# cj125.net
KiCad netlist of a schematic drawn in Altium Designer
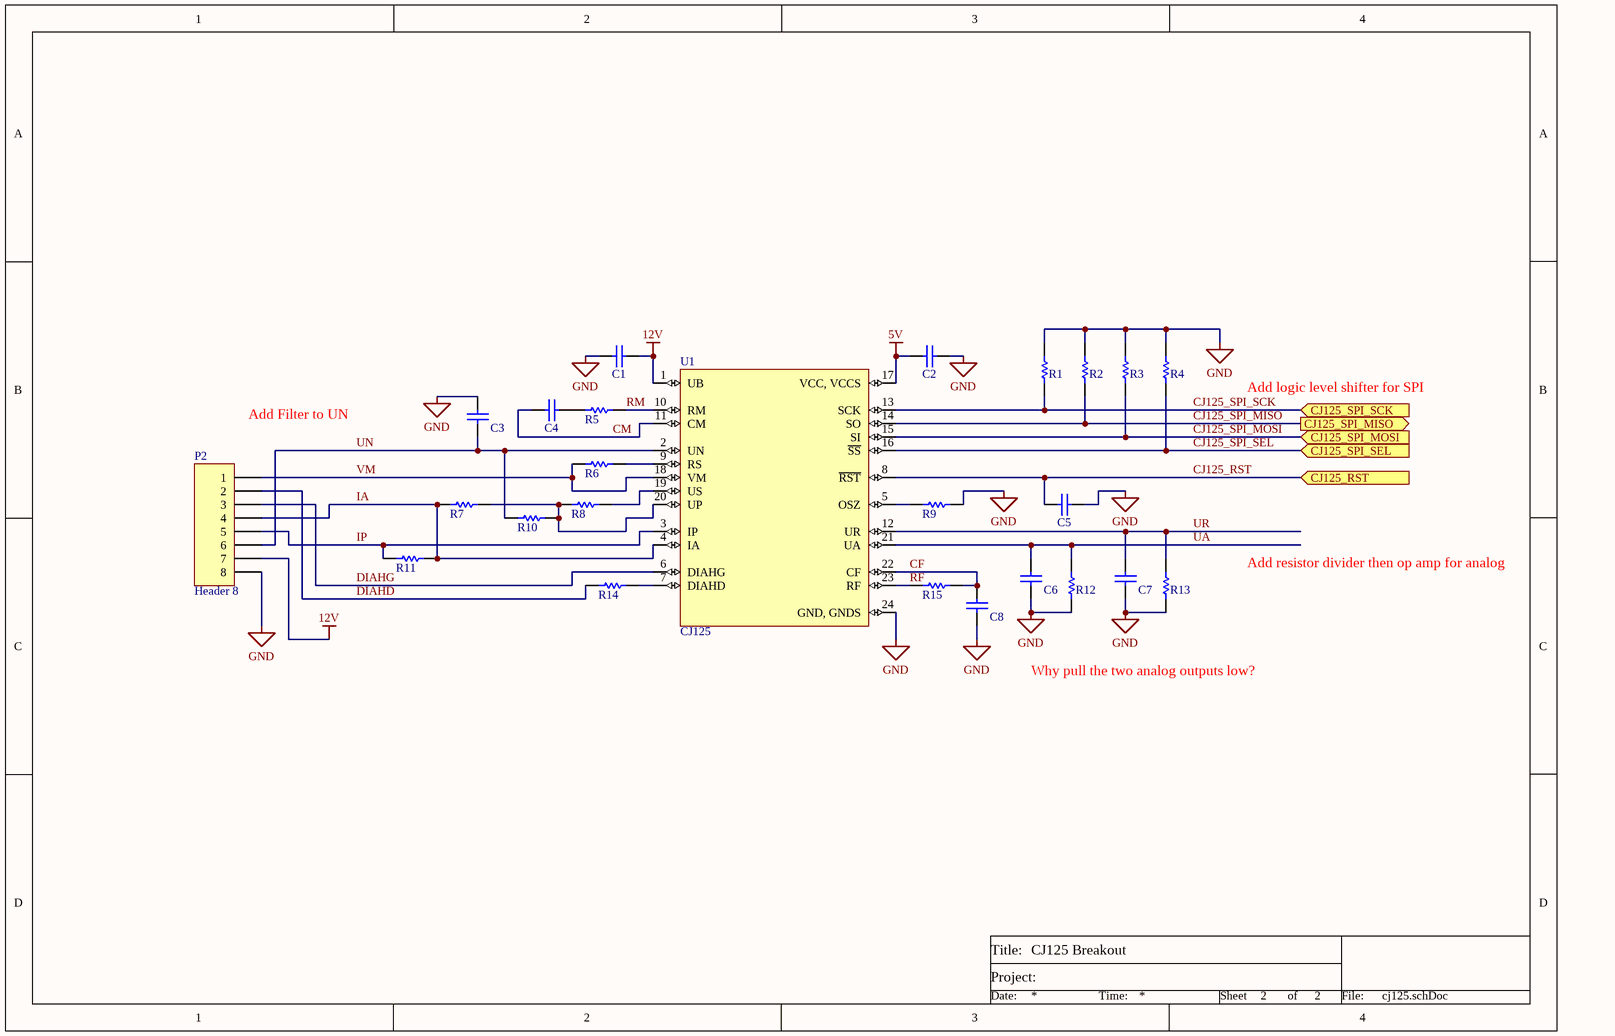
[diagram p0: cj125.schDoc]

(export (version "E")
  (design (tool "Eeschema 10.0.6"))
  (components
    (comp (ref "C1")
      (value "Generic 0805 Capacitor")
      (footprint "0805")
      (libsource (lib "symbol_library") (part "C_0805"))
    )
    (comp (ref "C2")
      (value "Generic 0805 Capacitor")
      (footprint "0805")
      (libsource (lib "symbol_library") (part "C_0805"))
    )
    (comp (ref "C3")
      (value "Generic 0805 Capacitor")
      (footprint "0805")
      (libsource (lib "symbol_library") (part "C_0805"))
    )
    (comp (ref "C4")
      (value "Generic 0805 Capacitor")
      (footprint "0805")
      (libsource (lib "symbol_library") (part "C_0805"))
    )
    (comp (ref "C5")
      (value "Generic 0805 Capacitor")
      (footprint "0805")
      (libsource (lib "symbol_library") (part "C_0805"))
    )
    (comp (ref "C6")
      (value "Generic 0805 Capacitor")
      (footprint "0805")
      (libsource (lib "symbol_library") (part "C_0805"))
    )
    (comp (ref "C7")
      (value "Generic 0805 Capacitor")
      (footprint "0805")
      (libsource (lib "symbol_library") (part "C_0805"))
    )
    (comp (ref "C8")
      (value "Generic 0805 Capacitor")
      (footprint "0805")
      (libsource (lib "symbol_library") (part "C_0805"))
    )
    (comp (ref "P2")
      (value "Header 8")
      (footprint "HDR1X8")
      (description "Header, 8-Pin")
      (fields (field (name "PUBLISHER") "Altium Limited"))
      (libsource (lib "Miscellaneous Connectors") (part "Header 8"))
    )
    (comp (ref "R1")
      (value "Generic 0603 Resistor")
      (footprint "0603")
      (libsource (lib "symbol_library") (part "R_0603"))
    )
    (comp (ref "R2")
      (value "Generic 0603 Resistor")
      (footprint "0603")
      (libsource (lib "symbol_library") (part "R_0603"))
    )
    (comp (ref "R3")
      (value "Generic 0603 Resistor")
      (footprint "0603")
      (libsource (lib "symbol_library") (part "R_0603"))
    )
    (comp (ref "R4")
      (value "Generic 0603 Resistor")
      (footprint "0603")
      (libsource (lib "symbol_library") (part "R_0603"))
    )
    (comp (ref "R5")
      (value "Generic 0603 Resistor")
      (footprint "0603")
      (libsource (lib "symbol_library") (part "R_0603"))
    )
    (comp (ref "R6")
      (value "Generic 0603 Resistor")
      (footprint "0603")
      (libsource (lib "symbol_library") (part "R_0603"))
    )
    (comp (ref "R7")
      (value "Generic 0603 Resistor")
      (footprint "0603")
      (libsource (lib "symbol_library") (part "R_0603"))
    )
    (comp (ref "R8")
      (value "Generic 0603 Resistor")
      (footprint "0603")
      (libsource (lib "symbol_library") (part "R_0603"))
    )
    (comp (ref "R9")
      (value "Generic 0603 Resistor")
      (footprint "0603")
      (libsource (lib "symbol_library") (part "R_0603"))
    )
    (comp (ref "R10")
      (value "Generic 0603 Resistor")
      (footprint "0603")
      (libsource (lib "symbol_library") (part "R_0603"))
    )
    (comp (ref "R11")
      (value "Generic 0603 Resistor")
      (footprint "0603")
      (libsource (lib "symbol_library") (part "R_0603"))
    )
    (comp (ref "R12")
      (value "Generic 0603 Resistor")
      (footprint "0603")
      (libsource (lib "symbol_library") (part "R_0603"))
    )
    (comp (ref "R13")
      (value "Generic 0603 Resistor")
      (footprint "0603")
      (libsource (lib "symbol_library") (part "R_0603"))
    )
    (comp (ref "R14")
      (value "Generic 0603 Resistor")
      (footprint "0603")
      (libsource (lib "symbol_library") (part "R_0603"))
    )
    (comp (ref "R15")
      (value "Generic 0603 Resistor")
      (footprint "0603")
      (libsource (lib "symbol_library") (part "R_0603"))
    )
    (comp (ref "U1")
      (value "CJ125")
      (footprint "SOIC-24")
      (description "5V 2Mbaud SMT Lambda Probe Interface IC - SOIC-24")
      (libsource (lib "symbol_library") (part "CJ125"))
    )
  )
  (nets
    (net (code "1") (name "/CF") (class "Default")
      (node (ref "C8") (pin "2") (pinfunction "2_2") (pintype "passive"))
      (node (ref "R15") (pin "2") (pinfunction "2_2") (pintype "passive"))
      (node (ref "U1") (pin "22") (pinfunction "CF_22") (pintype "bidirectional"))
    )
    (net (code "2") (name "/CJ125_RST") (class "Default")
      (node (ref "C5") (pin "1") (pinfunction "1_1") (pintype "passive"))
      (node (ref "U1") (pin "8") (pinfunction "~{RST}_8") (pintype "bidirectional"))
    )
    (net (code "3") (name "/CJ125_SPI_MISO") (class "Default")
      (node (ref "R2") (pin "1") (pinfunction "1_1") (pintype "passive"))
      (node (ref "U1") (pin "14") (pinfunction "SO_14") (pintype "bidirectional"))
    )
    (net (code "4") (name "/CJ125_SPI_MOSI") (class "Default")
      (node (ref "R3") (pin "1") (pinfunction "1_1") (pintype "passive"))
      (node (ref "U1") (pin "15") (pinfunction "SI_15") (pintype "bidirectional"))
    )
    (net (code "5") (name "/CJ125_SPI_SCK") (class "Default")
      (node (ref "R1") (pin "1") (pinfunction "1_1") (pintype "passive"))
      (node (ref "U1") (pin "13") (pinfunction "SCK_13") (pintype "bidirectional"))
    )
    (net (code "6") (name "/CJ125_SPI_SEL") (class "Default")
      (node (ref "R4") (pin "1") (pinfunction "1_1") (pintype "passive"))
      (node (ref "U1") (pin "16") (pinfunction "~{SS}_16") (pintype "bidirectional"))
    )
    (net (code "7") (name "/CM") (class "Default")
      (node (ref "C4") (pin "1") (pinfunction "1_1") (pintype "passive"))
      (node (ref "U1") (pin "11") (pinfunction "CM_11") (pintype "bidirectional"))
    )
    (net (code "8") (name "/DIAHD") (class "Default")
      (node (ref "P2") (pin "2") (pinfunction "2_2") (pintype "passive"))
      (node (ref "R14") (pin "1") (pinfunction "1_1") (pintype "passive"))
    )
    (net (code "9") (name "/DIAHG") (class "Default")
      (node (ref "P2") (pin "3") (pinfunction "3_3") (pintype "passive"))
      (node (ref "U1") (pin "6") (pinfunction "DIAHG_6") (pintype "bidirectional"))
    )
    (net (code "10") (name "/IA") (class "Default")
      (node (ref "P2") (pin "4") (pinfunction "4_4") (pintype "passive"))
      (node (ref "R11") (pin "2") (pinfunction "2_2") (pintype "passive"))
      (node (ref "R7") (pin "1") (pinfunction "1_1") (pintype "passive"))
      (node (ref "U1") (pin "4") (pinfunction "IA_4") (pintype "bidirectional"))
    )
    (net (code "11") (name "/IP") (class "Default")
      (node (ref "P2") (pin "5") (pinfunction "5_5") (pintype "passive"))
      (node (ref "R11") (pin "1") (pinfunction "1_1") (pintype "passive"))
      (node (ref "U1") (pin "3") (pinfunction "IP_3") (pintype "bidirectional"))
    )
    (net (code "12") (name "/RF") (class "Default")
      (node (ref "R15") (pin "1") (pinfunction "1_1") (pintype "passive"))
      (node (ref "U1") (pin "23") (pinfunction "RF_23") (pintype "bidirectional"))
    )
    (net (code "13") (name "/RM") (class "Default")
      (node (ref "R5") (pin "2") (pinfunction "2_2") (pintype "passive"))
      (node (ref "U1") (pin "10") (pinfunction "RM_10") (pintype "bidirectional"))
    )
    (net (code "14") (name "/UA") (class "Default")
      (node (ref "C6") (pin "2") (pinfunction "2_2") (pintype "passive"))
      (node (ref "R12") (pin "2") (pinfunction "2_2") (pintype "passive"))
      (node (ref "U1") (pin "21") (pinfunction "UA_21") (pintype "bidirectional"))
    )
    (net (code "15") (name "/UN") (class "Default")
      (node (ref "C3") (pin "1") (pinfunction "1_1") (pintype "passive"))
      (node (ref "P2") (pin "6") (pinfunction "6_6") (pintype "passive"))
      (node (ref "R10") (pin "1") (pinfunction "1_1") (pintype "passive"))
      (node (ref "U1") (pin "2") (pinfunction "UN_2") (pintype "bidirectional"))
    )
    (net (code "16") (name "/UR") (class "Default")
      (node (ref "C7") (pin "2") (pinfunction "2_2") (pintype "passive"))
      (node (ref "R13") (pin "2") (pinfunction "2_2") (pintype "passive"))
      (node (ref "U1") (pin "12") (pinfunction "UR_12") (pintype "bidirectional"))
    )
    (net (code "17") (name "/VM") (class "Default")
      (node (ref "P2") (pin "1") (pinfunction "1_1") (pintype "passive"))
      (node (ref "R6") (pin "1") (pinfunction "1_1") (pintype "passive"))
      (node (ref "U1") (pin "18") (pinfunction "VM_18") (pintype "bidirectional"))
    )
    (net (code "18") (name "5V") (class "Default")
      (node (ref "C2") (pin "1") (pinfunction "1_1") (pintype "passive"))
      (node (ref "U1") (pin "17") (pinfunction "VCC,_VCCS_17") (pintype "bidirectional"))
    )
    (net (code "19") (name "12V") (class "Default")
      (node (ref "C1") (pin "2") (pinfunction "2_2") (pintype "passive"))
      (node (ref "P2") (pin "7") (pinfunction "7_7") (pintype "passive"))
      (node (ref "U1") (pin "1") (pinfunction "UB_1") (pintype "bidirectional"))
    )
    (net (code "20") (name "GND") (class "Default")
      (node (ref "C1") (pin "1") (pinfunction "1_1") (pintype "passive"))
      (node (ref "C2") (pin "2") (pinfunction "2_2") (pintype "passive"))
      (node (ref "C3") (pin "2") (pinfunction "2_2") (pintype "passive"))
      (node (ref "C5") (pin "2") (pinfunction "2_2") (pintype "passive"))
      (node (ref "C6") (pin "1") (pinfunction "1_1") (pintype "passive"))
      (node (ref "C7") (pin "1") (pinfunction "1_1") (pintype "passive"))
      (node (ref "C8") (pin "1") (pinfunction "1_1") (pintype "passive"))
      (node (ref "P2") (pin "8") (pinfunction "8_8") (pintype "passive"))
      (node (ref "R1") (pin "2") (pinfunction "2_2") (pintype "passive"))
      (node (ref "R12") (pin "1") (pinfunction "1_1") (pintype "passive"))
      (node (ref "R13") (pin "1") (pinfunction "1_1") (pintype "passive"))
      (node (ref "R2") (pin "2") (pinfunction "2_2") (pintype "passive"))
      (node (ref "R3") (pin "2") (pinfunction "2_2") (pintype "passive"))
      (node (ref "R4") (pin "2") (pinfunction "2_2") (pintype "passive"))
      (node (ref "R9") (pin "2") (pinfunction "2_2") (pintype "passive"))
      (node (ref "U1") (pin "24") (pinfunction "GND,_GNDS_24") (pintype "bidirectional"))
    )
    (net (code "21") (name "Net-(C4-Pad2)") (class "Default")
      (node (ref "C4") (pin "2") (pinfunction "2_2") (pintype "passive"))
      (node (ref "R5") (pin "1") (pinfunction "1_1") (pintype "passive"))
    )
    (net (code "22") (name "Net-(U1-DIAHD)") (class "Default")
      (node (ref "R14") (pin "2") (pinfunction "2_2") (pintype "passive"))
      (node (ref "U1") (pin "7") (pinfunction "DIAHD_7") (pintype "bidirectional"))
    )
    (net (code "23") (name "Net-(U1-OSZ)") (class "Default")
      (node (ref "R9") (pin "1") (pinfunction "1_1") (pintype "passive"))
      (node (ref "U1") (pin "5") (pinfunction "OSZ_5") (pintype "bidirectional"))
    )
    (net (code "24") (name "Net-(U1-RS)") (class "Default")
      (node (ref "R6") (pin "2") (pinfunction "2_2") (pintype "passive"))
      (node (ref "U1") (pin "9") (pinfunction "RS_9") (pintype "bidirectional"))
    )
    (net (code "25") (name "Net-(U1-UP)") (class "Default")
      (node (ref "R10") (pin "2") (pinfunction "2_2") (pintype "passive"))
      (node (ref "R7") (pin "2") (pinfunction "2_2") (pintype "passive"))
      (node (ref "R8") (pin "1") (pinfunction "1_1") (pintype "passive"))
      (node (ref "U1") (pin "20") (pinfunction "UP_20") (pintype "bidirectional"))
    )
    (net (code "26") (name "Net-(U1-US)") (class "Default")
      (node (ref "R8") (pin "2") (pinfunction "2_2") (pintype "passive"))
      (node (ref "U1") (pin "19") (pinfunction "US_19") (pintype "bidirectional"))
    )
  )
)
